# Buck_Convertor_Design.net
KiCad netlist of a schematic drawn in EAGLE
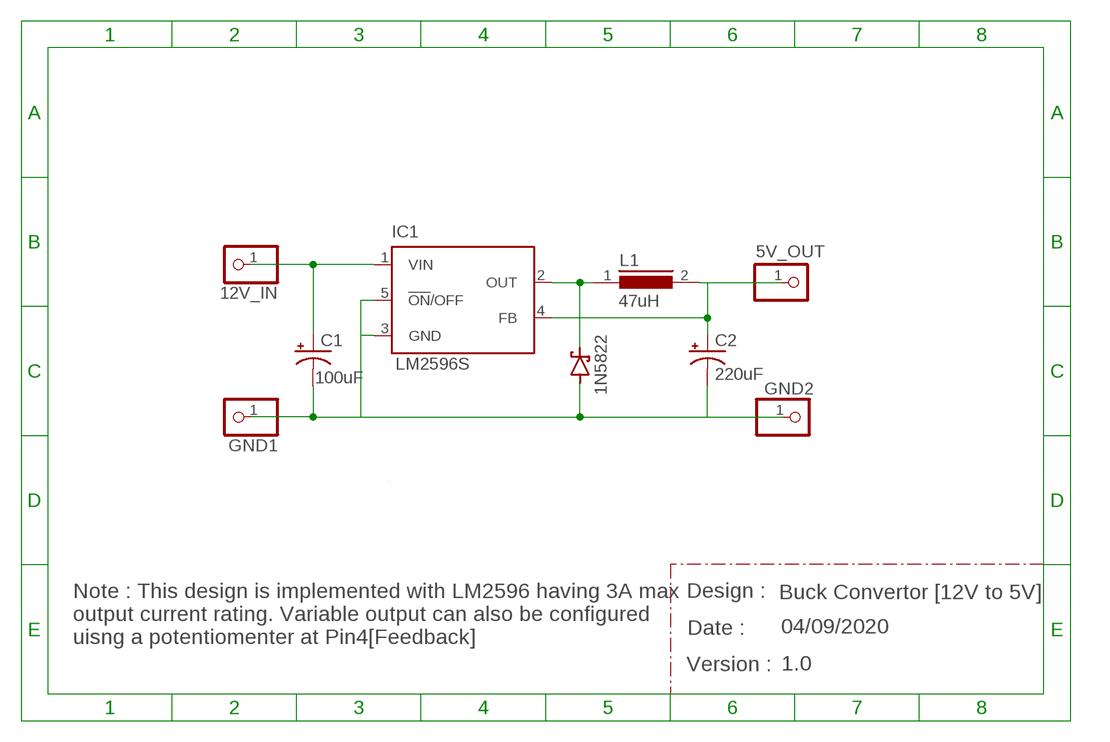
[diagram p0: schematic, sheet 1]

(export (version "E")
  (design (tool "Eeschema 10.0.6"))
  (components
    (comp (ref "5V_OUT")
      (value "PINHD-1X1")
      (footprint "eagle-import:1X01")
      (libsource (lib "eagle-import") (part "PINHD-1X1"))
    )
    (comp (ref "12V_IN")
      (value "PINHD-1X1")
      (footprint "eagle-import:1X01")
      (libsource (lib "eagle-import") (part "PINHD-1X1"))
    )
    (comp (ref "C1")
      (value "100uF")
      (footprint "eagle-import:140CLH-1010")
      (libsource (lib "eagle-import") (part "CPOL-US140CLH-1010"))
    )
    (comp (ref "C2")
      (value "220uF")
      (footprint "eagle-import:140CLH-1010")
      (libsource (lib "eagle-import") (part "CPOL-US140CLH-1010"))
    )
    (comp (ref "D6")
      (value "1N5822")
      (footprint "eagle-import:SMC")
      (libsource (lib "eagle-import") (part "SCHOTTKY-DIODESMC"))
    )
    (comp (ref "GND1")
      (value "PINHD-1X1")
      (footprint "eagle-import:1X01")
      (libsource (lib "eagle-import") (part "PINHD-1X1"))
    )
    (comp (ref "GND2")
      (value "PINHD-1X1")
      (footprint "eagle-import:1X01")
      (libsource (lib "eagle-import") (part "PINHD-1X1"))
    )
    (comp (ref "IC1")
      (value "LM2596S")
      (footprint "eagle-import:TO263-5")
      (fields (field (name "MF") "NATIONAL SEMICONDUCTOR") (field (name "MPN") "LM2596S-ADJ/NOPB"))
      (libsource (lib "eagle-import") (part "LM2596S"))
    )
    (comp (ref "L1")
      (value "47uH")
      (footprint "eagle-import:DR127")
      (libsource (lib "eagle-import") (part "DR127"))
    )
  )
  (nets
    (net (code "1") (name "Net-(IC1-FB)") (class "Default")
      (node (ref "5V_OUT") (pin "1") (pinfunction "1_1") (pintype "passive"))
      (node (ref "C2") (pin "+") (pinfunction "+_+") (pintype "passive"))
      (node (ref "IC1") (pin "4") (pinfunction "FB_4") (pintype "input"))
      (node (ref "L1") (pin "2") (pinfunction "2_2") (pintype "passive"))
    )
    (net (code "2") (name "Net-(IC1-GND)") (class "Default")
      (node (ref "C1") (pin "-") (pinfunction "-_-") (pintype "passive"))
      (node (ref "C2") (pin "-") (pinfunction "-_-") (pintype "passive"))
      (node (ref "D6") (pin "A") (pinfunction "A_A") (pintype "passive"))
      (node (ref "GND1") (pin "1") (pinfunction "1_1") (pintype "passive"))
      (node (ref "GND2") (pin "1") (pinfunction "1_1") (pintype "passive"))
      (node (ref "IC1") (pin "3") (pinfunction "GND_3") (pintype "power_in"))
      (node (ref "IC1") (pin "5") (pinfunction "~{ON}/OFF_5") (pintype "input"))
    )
    (net (code "3") (name "Net-(IC1-OUT)") (class "Default")
      (node (ref "D6") (pin "C") (pinfunction "C_C") (pintype "passive"))
      (node (ref "IC1") (pin "2") (pinfunction "OUT_2") (pintype "output"))
      (node (ref "L1") (pin "1") (pinfunction "1_1") (pintype "passive"))
    )
    (net (code "4") (name "Net-(IC1-VIN)") (class "Default")
      (node (ref "12V_IN") (pin "1") (pinfunction "1_1") (pintype "passive"))
      (node (ref "C1") (pin "+") (pinfunction "+_+") (pintype "passive"))
      (node (ref "IC1") (pin "1") (pinfunction "VIN_1") (pintype "input"))
    )
  )
)
